# shield_schematic.net
KiCad netlist of a schematic drawn in EAGLE
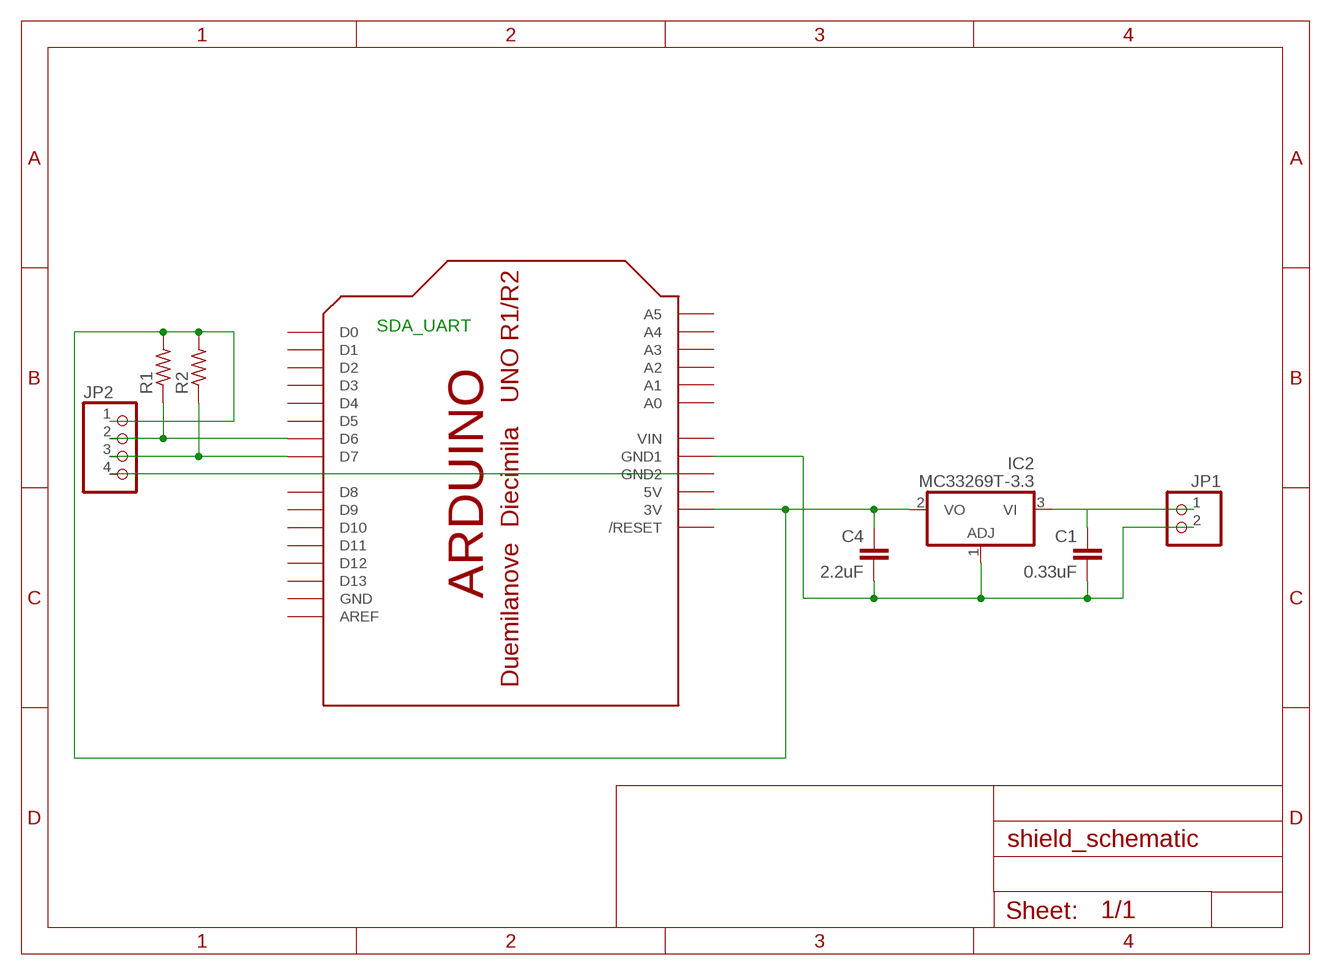
[diagram p0: schematic, sheet 1]

(export (version "E")
  (design (tool "Eeschema 10.0.6"))
  (components
    (comp (ref "C1")
      (value "0.33uF")
      (footprint "eagle-import:C5B2.5")
      (libsource (lib "eagle-import") (part "C5/2.5"))
    )
    (comp (ref "C4")
      (value "2.2uF")
      (footprint "eagle-import:C5B2.5")
      (libsource (lib "eagle-import") (part "C5/2.5"))
    )
    (comp (ref "IC2")
      (value "MC33269T-3.3")
      (footprint "eagle-import:TO220V")
      (libsource (lib "eagle-import") (part "MC33269?T-3.3"))
    )
    (comp (ref "JP1")
      (value "PINHD-1X2")
      (footprint "eagle-import:1X02")
      (libsource (lib "eagle-import") (part "PINHD-1X2"))
    )
    (comp (ref "JP2")
      (value "PINHD-1X4")
      (footprint "eagle-import:1X04")
      (libsource (lib "eagle-import") (part "PINHD-1X4"))
    )
    (comp (ref "R1")
      (value "R-US_0204/7")
      (footprint "eagle-import:0204_7")
      (libsource (lib "eagle-import") (part "R-US_0204/7"))
    )
    (comp (ref "R2")
      (value "R-US_0204/7")
      (footprint "eagle-import:0204_7")
      (libsource (lib "eagle-import") (part "R-US_0204/7"))
    )
    (comp (ref "U$1")
      (value "ARDUINO-BPLACE")
      (footprint "eagle-import:ARDUINO-BPLACE")
      (libsource (lib "eagle-import") (part "ARDUINO-BPLACE"))
    )
  )
  (nets
    (net (code "1") (name "/5V") (class "Default")
      (node (ref "U$1") (pin "5V") (pinfunction "5V_5V") (pintype "power_in"))
    )
    (net (code "2") (name "/GND") (class "Default")
      (node (ref "U$1") (pin "GND") (pinfunction "GND_GND") (pintype "power_in"))
    )
    (net (code "3") (name "/GND2") (class "Default")
      (node (ref "U$1") (pin "GND2") (pinfunction "GND2_GND2") (pintype "power_in"))
    )
    (net (code "4") (name "/VIN") (class "Default")
      (node (ref "U$1") (pin "VIN") (pinfunction "VIN_VIN") (pintype "power_in"))
    )
    (net (code "5") (name "Net-(IC2-ADJ)") (class "Default")
      (node (ref "C1") (pin "2") (pinfunction "2_2") (pintype "passive"))
      (node (ref "C4") (pin "2") (pinfunction "2_2") (pintype "passive"))
      (node (ref "IC2") (pin "1") (pinfunction "ADJ_1") (pintype "input"))
      (node (ref "JP1") (pin "2") (pinfunction "2_2") (pintype "passive"))
      (node (ref "U$1") (pin "GND1") (pinfunction "GND1_GND1") (pintype "power_in"))
    )
    (net (code "6") (name "Net-(IC2-VI)") (class "Default")
      (node (ref "C1") (pin "1") (pinfunction "1_1") (pintype "passive"))
      (node (ref "IC2") (pin "3") (pinfunction "VI_3") (pintype "input"))
      (node (ref "JP1") (pin "1") (pinfunction "1_1") (pintype "passive"))
    )
    (net (code "7") (name "Net-(IC2-VO)") (class "Default")
      (node (ref "C4") (pin "1") (pinfunction "1_1") (pintype "passive"))
      (node (ref "IC2") (pin "2") (pinfunction "VO_2") (pintype "passive"))
      (node (ref "JP2") (pin "1") (pinfunction "1_1") (pintype "passive"))
      (node (ref "R1") (pin "2") (pinfunction "2_2") (pintype "passive"))
      (node (ref "R2") (pin "2") (pinfunction "2_2") (pintype "passive"))
      (node (ref "U$1") (pin "3V") (pinfunction "3V_3V") (pintype "power_in"))
    )
    (net (code "8") (name "Net-(JP2-Pad2)") (class "Default")
      (node (ref "JP2") (pin "2") (pinfunction "2_2") (pintype "passive"))
      (node (ref "R1") (pin "1") (pinfunction "1_1") (pintype "passive"))
      (node (ref "U$1") (pin "D6") (pinfunction "D6_D6") (pintype "bidirectional"))
    )
    (net (code "9") (name "Net-(JP2-Pad3)") (class "Default")
      (node (ref "JP2") (pin "3") (pinfunction "3_3") (pintype "passive"))
      (node (ref "R2") (pin "1") (pinfunction "1_1") (pintype "passive"))
      (node (ref "U$1") (pin "D7") (pinfunction "D7_D7") (pintype "bidirectional"))
    )
    (net (code "10") (name "unconnected-(JP2-Pad4)") (class "Default")
      (node (ref "JP2") (pin "4") (pinfunction "4_4") (pintype "passive"))
    )
    (net (code "11") (name "unconnected-(U$1-PadA0)") (class "Default")
      (node (ref "U$1") (pin "A0") (pinfunction "A0_A0") (pintype "bidirectional"))
    )
    (net (code "12") (name "unconnected-(U$1-PadA1)") (class "Default")
      (node (ref "U$1") (pin "A1") (pinfunction "A1_A1") (pintype "bidirectional"))
    )
    (net (code "13") (name "unconnected-(U$1-PadA2)") (class "Default")
      (node (ref "U$1") (pin "A2") (pinfunction "A2_A2") (pintype "bidirectional"))
    )
    (net (code "14") (name "unconnected-(U$1-PadA3)") (class "Default")
      (node (ref "U$1") (pin "A3") (pinfunction "A3_A3") (pintype "bidirectional"))
    )
    (net (code "15") (name "unconnected-(U$1-PadA4)") (class "Default")
      (node (ref "U$1") (pin "A4") (pinfunction "A4_A4") (pintype "bidirectional"))
    )
    (net (code "16") (name "unconnected-(U$1-PadA5)") (class "Default")
      (node (ref "U$1") (pin "A5") (pinfunction "A5_A5") (pintype "bidirectional"))
    )
    (net (code "17") (name "unconnected-(U$1-PadAREF)") (class "Default")
      (node (ref "U$1") (pin "AREF") (pinfunction "AREF_AREF") (pintype "bidirectional"))
    )
    (net (code "18") (name "unconnected-(U$1-PadD0)") (class "Default")
      (node (ref "U$1") (pin "D0") (pinfunction "D0_D0") (pintype "bidirectional"))
    )
    (net (code "19") (name "unconnected-(U$1-PadD1)") (class "Default")
      (node (ref "U$1") (pin "D1") (pinfunction "D1_D1") (pintype "bidirectional"))
    )
    (net (code "20") (name "unconnected-(U$1-PadD2)") (class "Default")
      (node (ref "U$1") (pin "D2") (pinfunction "D2_D2") (pintype "bidirectional"))
    )
    (net (code "21") (name "unconnected-(U$1-PadD3)") (class "Default")
      (node (ref "U$1") (pin "D3") (pinfunction "D3_D3") (pintype "bidirectional"))
    )
    (net (code "22") (name "unconnected-(U$1-PadD4)") (class "Default")
      (node (ref "U$1") (pin "D4") (pinfunction "D4_D4") (pintype "bidirectional"))
    )
    (net (code "23") (name "unconnected-(U$1-PadD5)") (class "Default")
      (node (ref "U$1") (pin "D5") (pinfunction "D5_D5") (pintype "bidirectional"))
    )
    (net (code "24") (name "unconnected-(U$1-PadD8)") (class "Default")
      (node (ref "U$1") (pin "D8") (pinfunction "D8_D8") (pintype "bidirectional"))
    )
    (net (code "25") (name "unconnected-(U$1-PadD9)") (class "Default")
      (node (ref "U$1") (pin "D9") (pinfunction "D9_D9") (pintype "bidirectional"))
    )
    (net (code "26") (name "unconnected-(U$1-PadD10)") (class "Default")
      (node (ref "U$1") (pin "D10") (pinfunction "D10_D10") (pintype "bidirectional"))
    )
    (net (code "27") (name "unconnected-(U$1-PadD11)") (class "Default")
      (node (ref "U$1") (pin "D11") (pinfunction "D11_D11") (pintype "bidirectional"))
    )
    (net (code "28") (name "unconnected-(U$1-PadD12)") (class "Default")
      (node (ref "U$1") (pin "D12") (pinfunction "D12_D12") (pintype "bidirectional"))
    )
    (net (code "29") (name "unconnected-(U$1-PadD13)") (class "Default")
      (node (ref "U$1") (pin "D13") (pinfunction "D13_D13") (pintype "bidirectional"))
    )
    (net (code "30") (name "unconnected-(U$1-{slash}RESET-PadRESET)") (class "Default")
      (node (ref "U$1") (pin "RESET") (pinfunction "/RESET_RESET") (pintype "bidirectional"))
    )
  )
)
